# PIC32board.net
KiCad netlist of a schematic drawn in EAGLE
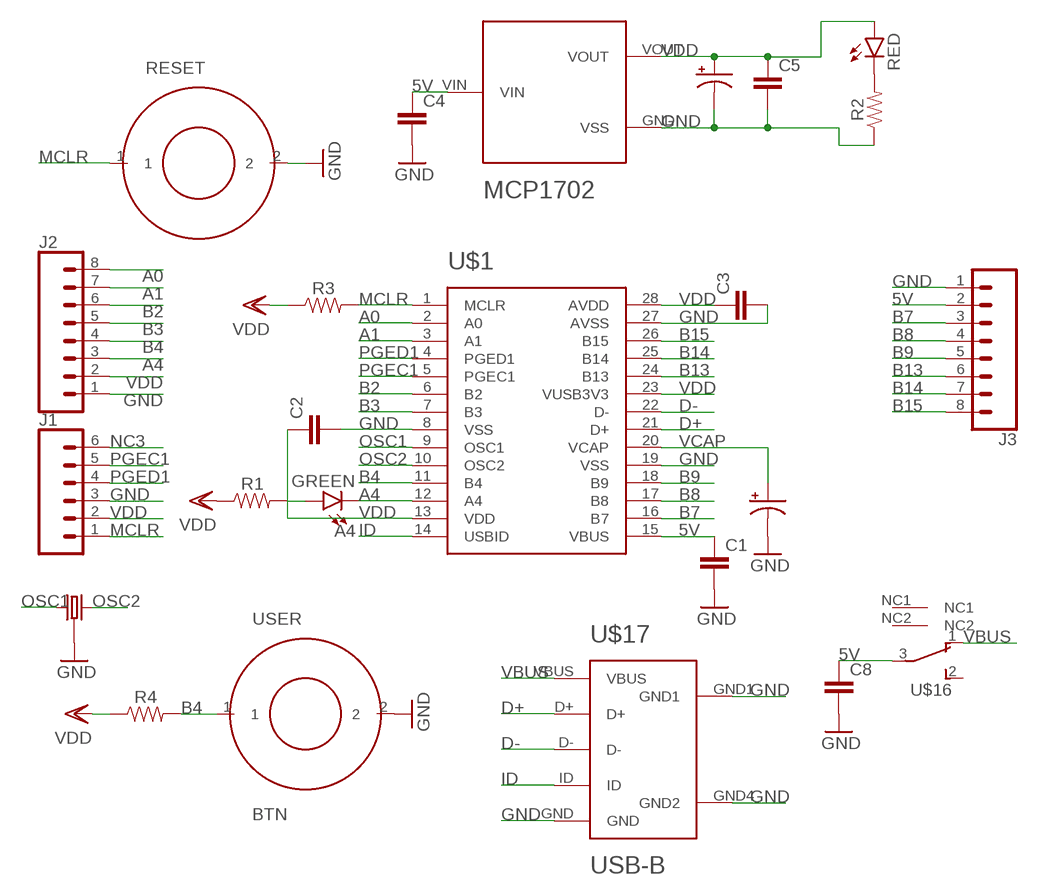
[diagram p0: schematic, sheet 1]

(export (version "E")
  (design (tool "Eeschema 10.0.6"))
  (components
    (comp (ref "A4")
      (value "GREEN")
      (footprint "eagle-import:LED-0603")
      (libsource (lib "eagle-import") (part "LED-GREEN0603"))
    )
    (comp (ref "C1")
      (value "0.1µF-SMD")
      (footprint "eagle-import:0603")
      (libsource (lib "eagle-import") (part "0.1µF-SMD"))
    )
    (comp (ref "C2")
      (value "0.1µF-SMD")
      (footprint "eagle-import:0603")
      (libsource (lib "eagle-import") (part "0.1µF-SMD"))
    )
    (comp (ref "C3")
      (value "0.1µF-SMD")
      (footprint "eagle-import:0603")
      (libsource (lib "eagle-import") (part "0.1µF-SMD"))
    )
    (comp (ref "C4")
      (value "0.1µF-SMD")
      (footprint "eagle-import:0603")
      (libsource (lib "eagle-import") (part "0.1µF-SMD"))
    )
    (comp (ref "C5")
      (value "0.1µF-SMD")
      (footprint "eagle-import:0603")
      (libsource (lib "eagle-import") (part "0.1µF-SMD"))
    )
    (comp (ref "C6")
      (value "10µF-POL")
      (footprint "eagle-import:10µF_THROUGHHOLE")
      (libsource (lib "eagle-import") (part "10µF-POL"))
    )
    (comp (ref "C7")
      (value "10µF-POL")
      (footprint "eagle-import:10µF_THROUGHHOLE")
      (libsource (lib "eagle-import") (part "10µF-POL"))
    )
    (comp (ref "C8")
      (value "0.1µF-SMD")
      (footprint "eagle-import:0603")
      (libsource (lib "eagle-import") (part "0.1µF-SMD"))
    )
    (comp (ref "J1")
      (value "CONN_06SILK_FEMALE_PTH")
      (footprint "eagle-import:1X06")
      (libsource (lib "eagle-import") (part "CONN_06SILK_FEMALE_PTH"))
    )
    (comp (ref "J2")
      (value "CONN_08\"")
      (footprint "eagle-import:1X08")
      (libsource (lib "eagle-import") (part "CONN_08{dblquote}"))
    )
    (comp (ref "J3")
      (value "CONN_08\"")
      (footprint "eagle-import:1X08")
      (libsource (lib "eagle-import") (part "CONN_08{dblquote}"))
    )
    (comp (ref "PWR")
      (value "RED")
      (footprint "eagle-import:LED-0603")
      (libsource (lib "eagle-import") (part "LED-RED0603"))
    )
    (comp (ref "R1")
      (value "330")
      (footprint "eagle-import:0603")
      (libsource (lib "eagle-import") (part "330OHM-0603-1/10W-1%"))
    )
    (comp (ref "R2")
      (value "330")
      (footprint "eagle-import:0603")
      (libsource (lib "eagle-import") (part "330OHM-0603-1/10W-1%"))
    )
    (comp (ref "R3")
      (value "10KOHM-SMD")
      (footprint "eagle-import:0603")
      (libsource (lib "eagle-import") (part "10KOHM-SMD"))
    )
    (comp (ref "R4")
      (value "10KOHM-SMD")
      (footprint "eagle-import:0603")
      (libsource (lib "eagle-import") (part "10KOHM-SMD"))
    )
    (comp (ref "RESET")
      (value "BTN")
      (footprint "eagle-import:BTN")
      (libsource (lib "eagle-import") (part "BTN"))
    )
    (comp (ref "U$1")
      (value "PIC32MX250F128B_SOCKET")
      (footprint "eagle-import:DIP28")
      (libsource (lib "eagle-import") (part "PIC32MX250F128B_SOCKET"))
    )
    (comp (ref "U$2")
      (value "MCP1702")
      (footprint "eagle-import:TO92")
      (libsource (lib "eagle-import") (part "MCP1702"))
    )
    (comp (ref "U$8")
      (value "8MHZ-CRYSTAL")
      (footprint "eagle-import:8MHZ-CRYSTAL")
      (libsource (lib "eagle-import") (part "8MHZ-CRYSTAL"))
    )
    (comp (ref "U$16")
      (value "SLIDE-SWITCH")
      (footprint "eagle-import:SLIDE-SWITCH")
      (libsource (lib "eagle-import") (part "SLIDE-SWITCH"))
    )
    (comp (ref "U$17")
      (value "USB-B")
      (footprint "eagle-import:USB-MINIB-THM-MOLEX")
      (libsource (lib "eagle-import") (part "USB-B"))
    )
    (comp (ref "USER")
      (value "BTN")
      (footprint "eagle-import:BTN")
      (libsource (lib "eagle-import") (part "BTN"))
    )
  )
  (nets
    (net (code "1") (name "/5V") (class "Default")
      (node (ref "C1") (pin "1") (pinfunction "1_1") (pintype "passive"))
      (node (ref "C4") (pin "1") (pinfunction "1_1") (pintype "passive"))
      (node (ref "C8") (pin "1") (pinfunction "1_1") (pintype "passive"))
      (node (ref "J3") (pin "2") (pinfunction "2_2") (pintype "passive"))
      (node (ref "U$1") (pin "15") (pinfunction "VBUS_15") (pintype "bidirectional"))
      (node (ref "U$16") (pin "3") (pinfunction "3_3") (pintype "passive"))
      (node (ref "U$2") (pin "VIN") (pinfunction "VIN_VIN") (pintype "bidirectional"))
    )
    (net (code "2") (name "/A0") (class "Default")
      (node (ref "J2") (pin "8") (pinfunction "8_8") (pintype "passive"))
      (node (ref "U$1") (pin "2") (pinfunction "A0_2") (pintype "bidirectional"))
    )
    (net (code "3") (name "/A1") (class "Default")
      (node (ref "J2") (pin "7") (pinfunction "7_7") (pintype "passive"))
      (node (ref "U$1") (pin "3") (pinfunction "A1_3") (pintype "bidirectional"))
    )
    (net (code "4") (name "/A4") (class "Default")
      (node (ref "A4") (pin "C") (pinfunction "C_C") (pintype "passive"))
      (node (ref "J2") (pin "3") (pinfunction "3_3") (pintype "passive"))
      (node (ref "U$1") (pin "12") (pinfunction "A4_12") (pintype "bidirectional"))
    )
    (net (code "5") (name "/B2") (class "Default")
      (node (ref "J2") (pin "6") (pinfunction "6_6") (pintype "passive"))
      (node (ref "U$1") (pin "6") (pinfunction "B2_6") (pintype "bidirectional"))
    )
    (net (code "6") (name "/B3") (class "Default")
      (node (ref "J2") (pin "5") (pinfunction "5_5") (pintype "passive"))
      (node (ref "U$1") (pin "7") (pinfunction "B3_7") (pintype "bidirectional"))
    )
    (net (code "7") (name "/B4") (class "Default")
      (node (ref "J2") (pin "4") (pinfunction "4_4") (pintype "passive"))
      (node (ref "R4") (pin "2") (pinfunction "2_2") (pintype "passive"))
      (node (ref "U$1") (pin "11") (pinfunction "B4_11") (pintype "bidirectional"))
      (node (ref "USER") (pin "1") (pinfunction "1_1") (pintype "bidirectional"))
    )
    (net (code "8") (name "/B7") (class "Default")
      (node (ref "J3") (pin "3") (pinfunction "3_3") (pintype "passive"))
      (node (ref "U$1") (pin "16") (pinfunction "B7_16") (pintype "bidirectional"))
    )
    (net (code "9") (name "/B8") (class "Default")
      (node (ref "J3") (pin "4") (pinfunction "4_4") (pintype "passive"))
      (node (ref "U$1") (pin "17") (pinfunction "B8_17") (pintype "bidirectional"))
    )
    (net (code "10") (name "/B9") (class "Default")
      (node (ref "J3") (pin "5") (pinfunction "5_5") (pintype "passive"))
      (node (ref "U$1") (pin "18") (pinfunction "B9_18") (pintype "bidirectional"))
    )
    (net (code "11") (name "/B13") (class "Default")
      (node (ref "J3") (pin "6") (pinfunction "6_6") (pintype "passive"))
      (node (ref "U$1") (pin "24") (pinfunction "B13_24") (pintype "bidirectional"))
    )
    (net (code "12") (name "/B14") (class "Default")
      (node (ref "J3") (pin "7") (pinfunction "7_7") (pintype "passive"))
      (node (ref "U$1") (pin "25") (pinfunction "B14_25") (pintype "bidirectional"))
    )
    (net (code "13") (name "/B15") (class "Default")
      (node (ref "J3") (pin "8") (pinfunction "8_8") (pintype "passive"))
      (node (ref "U$1") (pin "26") (pinfunction "B15_26") (pintype "bidirectional"))
    )
    (net (code "14") (name "/D+") (class "Default")
      (node (ref "U$1") (pin "21") (pinfunction "D+_21") (pintype "bidirectional"))
      (node (ref "U$17") (pin "D+") (pinfunction "D+_D+") (pintype "bidirectional"))
    )
    (net (code "15") (name "/D-") (class "Default")
      (node (ref "U$1") (pin "22") (pinfunction "D-_22") (pintype "bidirectional"))
      (node (ref "U$17") (pin "D-") (pinfunction "D-_D-") (pintype "bidirectional"))
    )
    (net (code "16") (name "/ID") (class "Default")
      (node (ref "U$1") (pin "14") (pinfunction "USBID_14") (pintype "bidirectional"))
      (node (ref "U$17") (pin "ID") (pinfunction "ID_ID") (pintype "bidirectional"))
    )
    (net (code "17") (name "/MCLR") (class "Default")
      (node (ref "J1") (pin "1") (pinfunction "1_1") (pintype "passive"))
      (node (ref "R3") (pin "2") (pinfunction "2_2") (pintype "passive"))
      (node (ref "RESET") (pin "1") (pinfunction "1_1") (pintype "bidirectional"))
      (node (ref "U$1") (pin "1") (pinfunction "MCLR_1") (pintype "bidirectional"))
    )
    (net (code "18") (name "/NC3") (class "Default")
      (node (ref "J1") (pin "6") (pinfunction "6_6") (pintype "passive"))
    )
    (net (code "19") (name "/OSC1") (class "Default")
      (node (ref "U$1") (pin "9") (pinfunction "OSC1_9") (pintype "bidirectional"))
      (node (ref "U$8") (pin "1") (pinfunction "1_1") (pintype "passive"))
    )
    (net (code "20") (name "/OSC2") (class "Default")
      (node (ref "U$1") (pin "10") (pinfunction "OSC2_10") (pintype "bidirectional"))
      (node (ref "U$8") (pin "3") (pinfunction "2_3") (pintype "passive"))
    )
    (net (code "21") (name "/PGEC1") (class "Default")
      (node (ref "J1") (pin "5") (pinfunction "5_5") (pintype "passive"))
      (node (ref "U$1") (pin "5") (pinfunction "PGEC1_5") (pintype "bidirectional"))
    )
    (net (code "22") (name "/PGED1") (class "Default")
      (node (ref "J1") (pin "4") (pinfunction "4_4") (pintype "passive"))
      (node (ref "U$1") (pin "4") (pinfunction "PGED1_4") (pintype "bidirectional"))
    )
    (net (code "23") (name "/VBUS") (class "Default")
      (node (ref "U$16") (pin "1") (pinfunction "1_1") (pintype "passive"))
      (node (ref "U$17") (pin "VBUS") (pinfunction "VBUS_VBUS") (pintype "bidirectional"))
    )
    (net (code "24") (name "/VCAP") (class "Default")
      (node (ref "C7") (pin "POS") (pinfunction "+_POS") (pintype "passive"))
      (node (ref "U$1") (pin "20") (pinfunction "VCAP_20") (pintype "bidirectional"))
    )
    (net (code "25") (name "GND") (class "Default")
      (node (ref "C1") (pin "2") (pinfunction "2_2") (pintype "passive"))
      (node (ref "C2") (pin "2") (pinfunction "2_2") (pintype "passive"))
      (node (ref "C3") (pin "2") (pinfunction "2_2") (pintype "passive"))
      (node (ref "C4") (pin "2") (pinfunction "2_2") (pintype "passive"))
      (node (ref "C5") (pin "2") (pinfunction "2_2") (pintype "passive"))
      (node (ref "C6") (pin "NEG") (pinfunction "-_NEG") (pintype "passive"))
      (node (ref "C7") (pin "NEG") (pinfunction "-_NEG") (pintype "passive"))
      (node (ref "C8") (pin "2") (pinfunction "2_2") (pintype "passive"))
      (node (ref "J1") (pin "3") (pinfunction "3_3") (pintype "passive"))
      (node (ref "J2") (pin "1") (pinfunction "1_1") (pintype "passive"))
      (node (ref "J3") (pin "1") (pinfunction "1_1") (pintype "passive"))
      (node (ref "R2") (pin "1") (pinfunction "1_1") (pintype "passive"))
      (node (ref "RESET") (pin "2") (pinfunction "2_2") (pintype "bidirectional"))
      (node (ref "U$1") (pin "19") (pinfunction "VSS_19") (pintype "bidirectional"))
      (node (ref "U$1") (pin "27") (pinfunction "AVSS_27") (pintype "bidirectional"))
      (node (ref "U$1") (pin "8") (pinfunction "VSS_8") (pintype "bidirectional"))
      (node (ref "U$17") (pin "GND") (pinfunction "GND_GND") (pintype "bidirectional"))
      (node (ref "U$17") (pin "GND1") (pinfunction "GND1_GND1") (pintype "bidirectional"))
      (node (ref "U$17") (pin "GND4") (pinfunction "GND2_GND4") (pintype "bidirectional"))
      (node (ref "U$2") (pin "GND") (pinfunction "VSS_GND") (pintype "bidirectional"))
      (node (ref "U$8") (pin "2") (pinfunction "VSS_2") (pintype "passive"))
      (node (ref "USER") (pin "2") (pinfunction "2_2") (pintype "bidirectional"))
    )
    (net (code "26") (name "Net-(A4-PadA)") (class "Default")
      (node (ref "A4") (pin "A") (pinfunction "A_A") (pintype "passive"))
      (node (ref "R1") (pin "2") (pinfunction "2_2") (pintype "passive"))
    )
    (net (code "27") (name "Net-(PWR-PadC)") (class "Default")
      (node (ref "PWR") (pin "C") (pinfunction "C_C") (pintype "passive"))
      (node (ref "R2") (pin "2") (pinfunction "2_2") (pintype "passive"))
    )
    (net (code "28") (name "VDD") (class "Default")
      (node (ref "C2") (pin "1") (pinfunction "1_1") (pintype "passive"))
      (node (ref "C3") (pin "1") (pinfunction "1_1") (pintype "passive"))
      (node (ref "C5") (pin "1") (pinfunction "1_1") (pintype "passive"))
      (node (ref "C6") (pin "POS") (pinfunction "+_POS") (pintype "passive"))
      (node (ref "J1") (pin "2") (pinfunction "2_2") (pintype "passive"))
      (node (ref "J2") (pin "2") (pinfunction "2_2") (pintype "passive"))
      (node (ref "PWR") (pin "A") (pinfunction "A_A") (pintype "passive"))
      (node (ref "R1") (pin "1") (pinfunction "1_1") (pintype "passive"))
      (node (ref "R3") (pin "1") (pinfunction "1_1") (pintype "passive"))
      (node (ref "R4") (pin "1") (pinfunction "1_1") (pintype "passive"))
      (node (ref "U$1") (pin "13") (pinfunction "VDD_13") (pintype "bidirectional"))
      (node (ref "U$1") (pin "23") (pinfunction "VUSB3V3_23") (pintype "bidirectional"))
      (node (ref "U$1") (pin "28") (pinfunction "AVDD_28") (pintype "bidirectional"))
      (node (ref "U$2") (pin "VOUT") (pinfunction "VOUT_VOUT") (pintype "bidirectional"))
    )
    (net (code "29") (name "unconnected-(U$16-Pad2)") (class "Default")
      (node (ref "U$16") (pin "2") (pinfunction "2_2") (pintype "passive"))
    )
    (net (code "30") (name "unconnected-(U$16-PadNC1)") (class "Default")
      (node (ref "U$16") (pin "NC1") (pinfunction "NC1_NC1") (pintype "bidirectional"))
    )
    (net (code "31") (name "unconnected-(U$16-PadNC2)") (class "Default")
      (node (ref "U$16") (pin "NC2") (pinfunction "NC2_NC2") (pintype "bidirectional"))
    )
  )
)
